# Peripherals_-_MyoSensor.net
KiCad netlist of a schematic drawn in Altium Designer
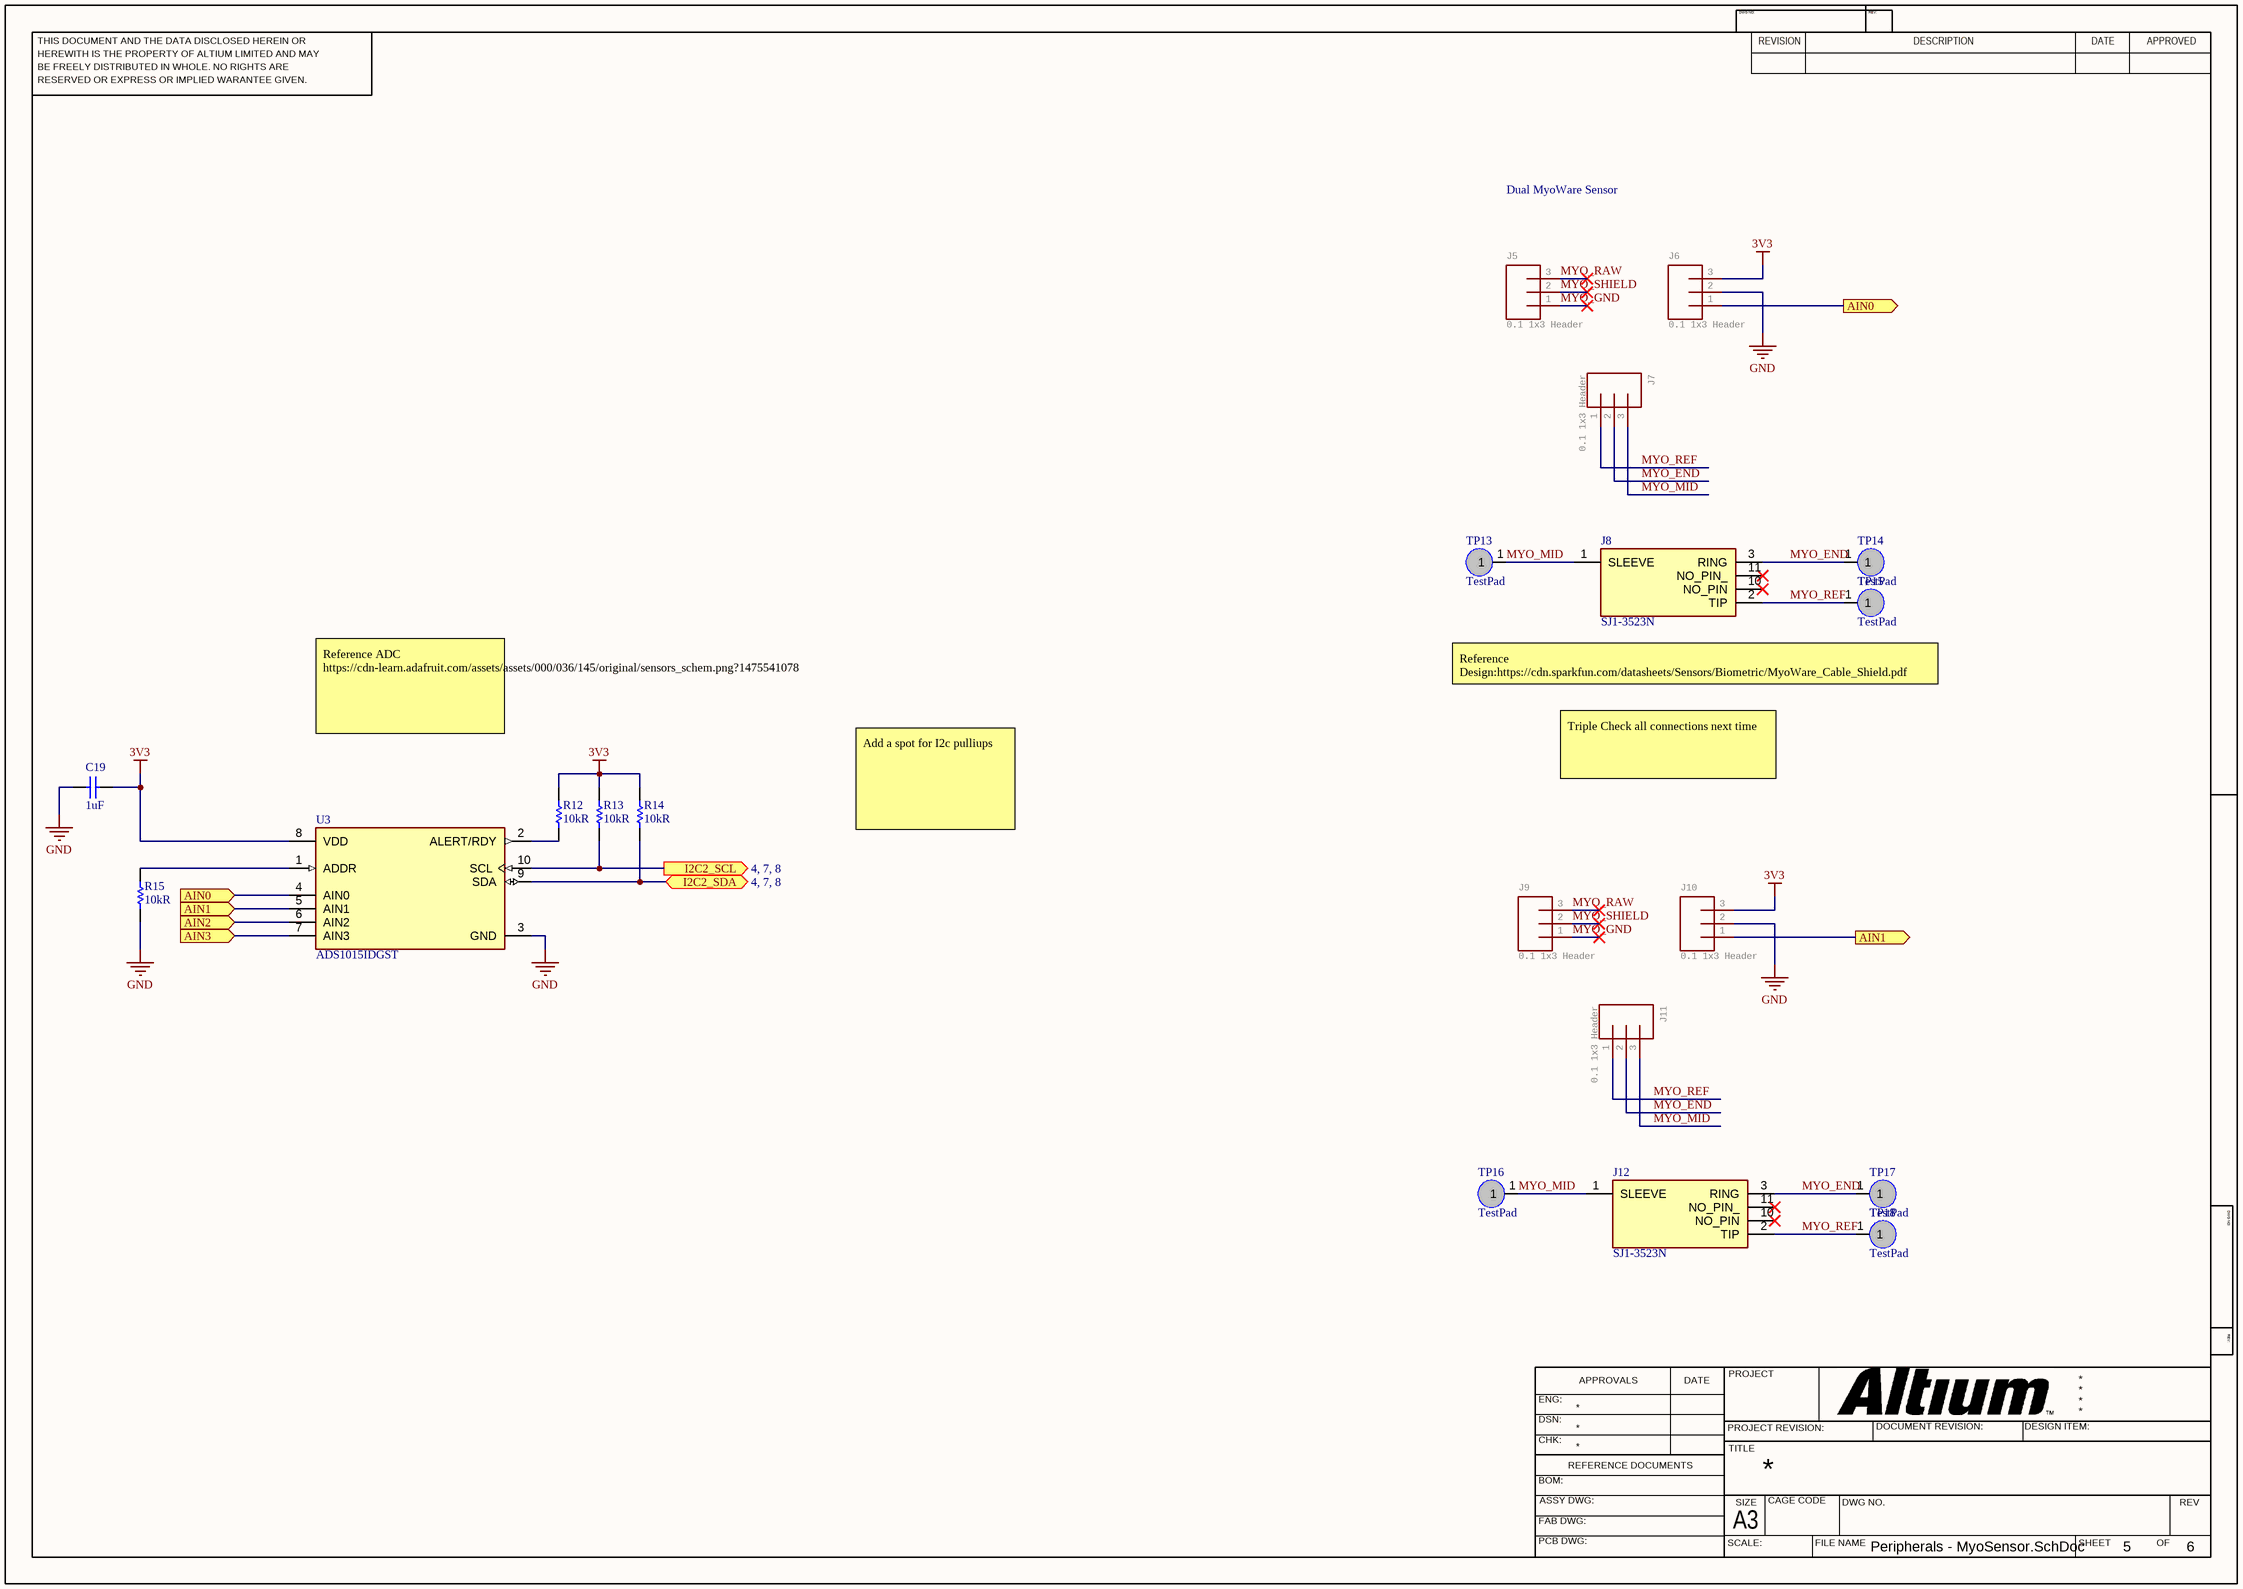
[diagram p0: Peripherals - MyoSensor.SchDoc]

(export (version "E")
  (design (tool "Eeschema 10.0.6"))
  (components
    (comp (ref "C19")
      (value "1uF")
      (footprint "CAPC2013X145X50LL20T25")
      (description "C0805C105K4PACTU")
      (fields (field (name "MANUFACTURER") "Kemet"))
      (libsource (lib "Altium Content Vault") (part "CAP"))
    )
    (comp (ref "J5")
      (value "0.1 1x3 Header")
      (footprint "1X03")
      (libsource (lib "SparkFun-Connectors.Library") (part "CONN_03"))
    )
    (comp (ref "J6")
      (value "0.1 1x3 Header")
      (footprint "1X03")
      (libsource (lib "SparkFun-Connectors.Library") (part "CONN_03"))
    )
    (comp (ref "J7")
      (value "0.1 1x3 Header")
      (footprint "1X03")
      (libsource (lib "SparkFun-Connectors.Library") (part "CONN_03"))
    )
    (comp (ref "J8")
      (value "SJ1-3523N")
      (footprint "LayoutFootprintsGoogle:SJ13523N")
      (description "Connector")
      (fields (field (name "MOUSER PART NUMBER") "490-SJ1-3523N"))
      (libsource (lib "*") (part "SJ1-3523N"))
    )
    (comp (ref "J9")
      (value "0.1 1x3 Header")
      (footprint "1X03")
      (libsource (lib "SparkFun-Connectors.Library") (part "CONN_03"))
    )
    (comp (ref "J10")
      (value "0.1 1x3 Header")
      (footprint "1X03")
      (libsource (lib "SparkFun-Connectors.Library") (part "CONN_03"))
    )
    (comp (ref "J11")
      (value "0.1 1x3 Header")
      (footprint "1X03")
      (libsource (lib "SparkFun-Connectors.Library") (part "CONN_03"))
    )
    (comp (ref "J12")
      (value "SJ1-3523N")
      (footprint "LayoutFootprintsGoogle:SJ13523N")
      (description "Connector")
      (fields (field (name "MOUSER PART NUMBER") "490-SJ1-3523N"))
      (libsource (lib "*") (part "SJ1-3523N"))
    )
    (comp (ref "R12")
      (value "10kR")
      (footprint "RESC2013X60X35NL10T20")
      (fields (field (name "MANUFACTURER") "Yageo"))
      (libsource (lib "Altium Content Vault") (part "RES-2"))
    )
    (comp (ref "R13")
      (value "10kR")
      (footprint "RESC2013X60X35NL10T20")
      (fields (field (name "MANUFACTURER") "Yageo"))
      (libsource (lib "Altium Content Vault") (part "RES-2"))
    )
    (comp (ref "R14")
      (value "10kR")
      (footprint "RESC2013X60X35NL10T20")
      (fields (field (name "MANUFACTURER") "Yageo"))
      (libsource (lib "Altium Content Vault") (part "RES-2"))
    )
    (comp (ref "R15")
      (value "10kR")
      (footprint "RESC2013X60X35NL10T20")
      (fields (field (name "MANUFACTURER") "Yageo"))
      (libsource (lib "Altium Content Vault") (part "RES-2"))
    )
    (comp (ref "TP13")
      (value "TestPad")
      (footprint "TestPad50mil")
      (libsource (lib "SchemSymbolsGoogle") (part "TestPad"))
    )
    (comp (ref "TP14")
      (value "TestPad")
      (footprint "TestPad50mil")
      (libsource (lib "SchemSymbolsGoogle") (part "TestPad"))
    )
    (comp (ref "TP15")
      (value "TestPad")
      (footprint "TestPad50mil")
      (libsource (lib "SchemSymbolsGoogle") (part "TestPad"))
    )
    (comp (ref "TP16")
      (value "TestPad")
      (footprint "TestPad50mil")
      (libsource (lib "SchemSymbolsGoogle") (part "TestPad"))
    )
    (comp (ref "TP17")
      (value "TestPad")
      (footprint "TestPad50mil")
      (libsource (lib "SchemSymbolsGoogle") (part "TestPad"))
    )
    (comp (ref "TP18")
      (value "TestPad")
      (footprint "TestPad50mil")
      (libsource (lib "SchemSymbolsGoogle") (part "TestPad"))
    )
    (comp (ref "U3")
      (value "ADS1015IDGST")
      (footprint "FP-DGS0010A-MFG")
      (description "IC ADC 12BIT SIGMA-DELTA 10VSSOP")
      (libsource (lib "Altium Content Vault") (part "0fb225032f4bd54fd540a872e776a50"))
    )
  )
  (nets
    (net (code "1") (name "/AIN0") (class "Default")
      (node (ref "J6") (pin "1") (pinfunction "1_1") (pintype "passive"))
      (node (ref "U3") (pin "4") (pinfunction "AIN0_4") (pintype "passive"))
    )
    (net (code "2") (name "/AIN1") (class "Default")
      (node (ref "J10") (pin "1") (pinfunction "1_1") (pintype "passive"))
      (node (ref "U3") (pin "5") (pinfunction "AIN1_5") (pintype "passive"))
    )
    (net (code "3") (name "/AIN2") (class "Default")
      (node (ref "U3") (pin "6") (pinfunction "AIN2_6") (pintype "passive"))
    )
    (net (code "4") (name "/AIN3") (class "Default")
      (node (ref "U3") (pin "7") (pinfunction "AIN3_7") (pintype "passive"))
    )
    (net (code "5") (name "/I2C2_SCL") (class "Default")
      (node (ref "R13") (pin "1") (pinfunction "1_1") (pintype "passive"))
      (node (ref "U3") (pin "10") (pinfunction "SCL_10") (pintype "input"))
    )
    (net (code "6") (name "/I2C2_SDA") (class "Default")
      (node (ref "R14") (pin "1") (pinfunction "1_1") (pintype "passive"))
      (node (ref "U3") (pin "9") (pinfunction "SDA_9") (pintype "bidirectional"))
    )
    (net (code "7") (name "/MYO_END") (class "Default")
      (node (ref "J11") (pin "2") (pinfunction "2_2") (pintype "passive"))
      (node (ref "J12") (pin "3") (pinfunction "RING_3") (pintype "passive"))
      (node (ref "J7") (pin "2") (pinfunction "2_2") (pintype "passive"))
      (node (ref "J8") (pin "3") (pinfunction "RING_3") (pintype "passive"))
      (node (ref "TP14") (pin "1") (pinfunction "1_1") (pintype "passive"))
      (node (ref "TP17") (pin "1") (pinfunction "1_1") (pintype "passive"))
    )
    (net (code "8") (name "/MYO_GND") (class "Default")
      (node (ref "J5") (pin "1") (pinfunction "1_1") (pintype "passive"))
      (node (ref "J9") (pin "1") (pinfunction "1_1") (pintype "passive"))
    )
    (net (code "9") (name "/MYO_MID") (class "Default")
      (node (ref "J11") (pin "3") (pinfunction "3_3") (pintype "passive"))
      (node (ref "J12") (pin "1") (pinfunction "SLEEVE_1") (pintype "passive"))
      (node (ref "J7") (pin "3") (pinfunction "3_3") (pintype "passive"))
      (node (ref "J8") (pin "1") (pinfunction "SLEEVE_1") (pintype "passive"))
      (node (ref "TP13") (pin "1") (pinfunction "1_1") (pintype "passive"))
      (node (ref "TP16") (pin "1") (pinfunction "1_1") (pintype "passive"))
    )
    (net (code "10") (name "/MYO_RAW") (class "Default")
      (node (ref "J5") (pin "3") (pinfunction "3_3") (pintype "passive"))
      (node (ref "J9") (pin "3") (pinfunction "3_3") (pintype "passive"))
    )
    (net (code "11") (name "/MYO_REF") (class "Default")
      (node (ref "J11") (pin "1") (pinfunction "1_1") (pintype "passive"))
      (node (ref "J12") (pin "2") (pinfunction "TIP_2") (pintype "passive"))
      (node (ref "J7") (pin "1") (pinfunction "1_1") (pintype "passive"))
      (node (ref "J8") (pin "2") (pinfunction "TIP_2") (pintype "passive"))
      (node (ref "TP15") (pin "1") (pinfunction "1_1") (pintype "passive"))
      (node (ref "TP18") (pin "1") (pinfunction "1_1") (pintype "passive"))
    )
    (net (code "12") (name "/MYO_SHIELD") (class "Default")
      (node (ref "J5") (pin "2") (pinfunction "2_2") (pintype "passive"))
      (node (ref "J9") (pin "2") (pinfunction "2_2") (pintype "passive"))
    )
    (net (code "13") (name "3V3") (class "Default")
      (node (ref "C19") (pin "2") (pinfunction "2_2") (pintype "passive"))
      (node (ref "J10") (pin "3") (pinfunction "3_3") (pintype "passive"))
      (node (ref "J6") (pin "3") (pinfunction "3_3") (pintype "passive"))
      (node (ref "R12") (pin "2") (pinfunction "2_2") (pintype "passive"))
      (node (ref "R13") (pin "2") (pinfunction "2_2") (pintype "passive"))
      (node (ref "R14") (pin "2") (pinfunction "2_2") (pintype "passive"))
      (node (ref "U3") (pin "8") (pinfunction "VDD_8") (pintype "power_in"))
    )
    (net (code "14") (name "GND") (class "Default")
      (node (ref "C19") (pin "1") (pinfunction "1_1") (pintype "passive"))
      (node (ref "J10") (pin "2") (pinfunction "2_2") (pintype "passive"))
      (node (ref "J6") (pin "2") (pinfunction "2_2") (pintype "passive"))
      (node (ref "R15") (pin "1") (pinfunction "1_1") (pintype "passive"))
      (node (ref "U3") (pin "3") (pinfunction "GND_3") (pintype "power_in"))
    )
    (net (code "15") (name "Net-(U3-ADDR)") (class "Default")
      (node (ref "R15") (pin "2") (pinfunction "2_2") (pintype "passive"))
      (node (ref "U3") (pin "1") (pinfunction "ADDR_1") (pintype "input"))
    )
    (net (code "16") (name "Net-(U3-ALERT{slash}RDY)") (class "Default")
      (node (ref "R12") (pin "1") (pinfunction "1_1") (pintype "passive"))
      (node (ref "U3") (pin "2") (pinfunction "ALERT/RDY_2") (pintype "output"))
    )
    (net (code "17") (name "unconnected-(J8-NO_PIN-Pad10)") (class "Default")
      (node (ref "J8") (pin "10") (pinfunction "NO_PIN_10") (pintype "passive+no_connect"))
    )
    (net (code "18") (name "unconnected-(J8-NO_PIN_-Pad11)") (class "Default")
      (node (ref "J8") (pin "11") (pinfunction "NO_PIN__11") (pintype "passive+no_connect"))
    )
    (net (code "19") (name "unconnected-(J12-NO_PIN-Pad10)") (class "Default")
      (node (ref "J12") (pin "10") (pinfunction "NO_PIN_10") (pintype "passive+no_connect"))
    )
    (net (code "20") (name "unconnected-(J12-NO_PIN_-Pad11)") (class "Default")
      (node (ref "J12") (pin "11") (pinfunction "NO_PIN__11") (pintype "passive+no_connect"))
    )
  )
)
